# Power_managment.net
KiCad netlist of a schematic drawn in Altium Designer
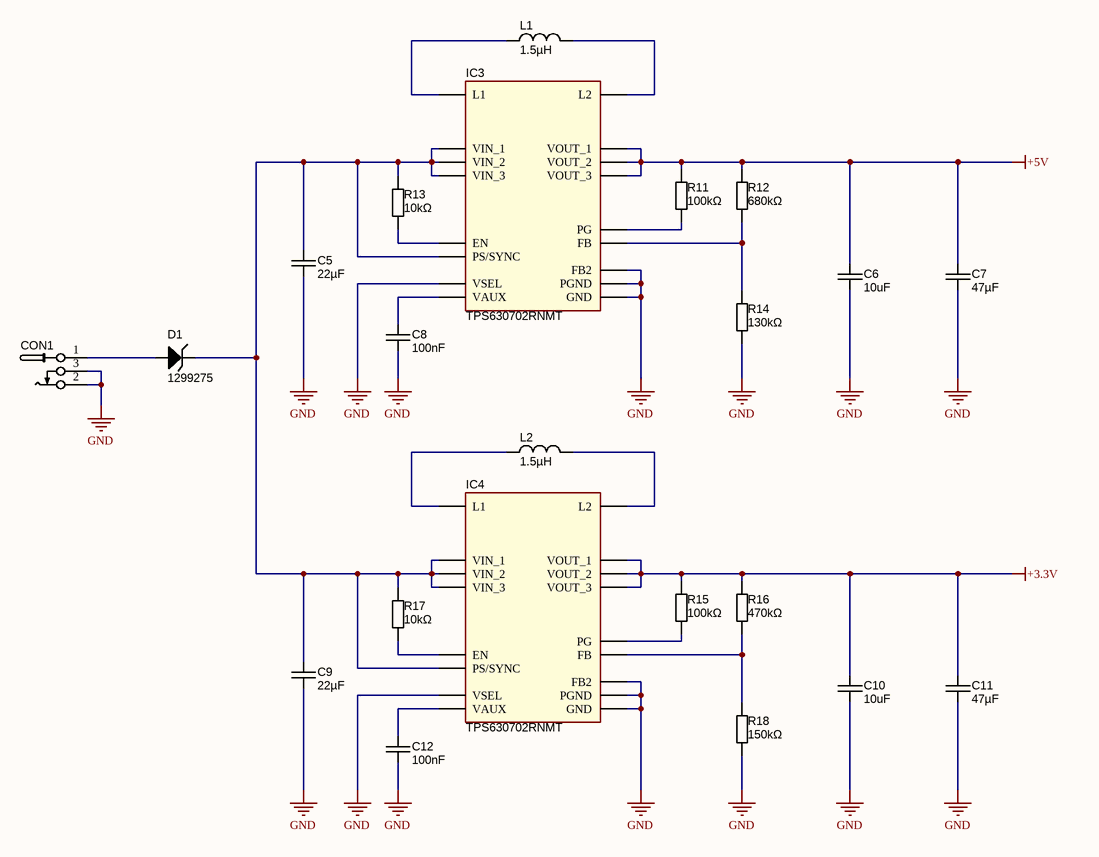
[diagram p0: Power managment.SchDoc]

(export (version "E")
  (design (tool "Eeschema 10.0.6"))
  (components
    (comp (ref "C5")
      (value "22µF")
      (footprint "CAPC3216N")
      (description "Capacitor SMD Cer 10uF 10% 16V X7R 1206")
      (fields (field (name "TOLERANCE") "±10%") (field (name "Comment") "approved sub OK"))
      (libsource (lib "Nejc Klanjšček") (part "CAPC_10u_1206_16V"))
    )
    (comp (ref "C6")
      (value "10uF")
      (footprint "CAPC1608N")
      (description "Capacitor SMD Cer 1uF 10% 16V X7R 0603")
      (fields (field (name "TOLERANCE") "±10%") (field (name "Comment") "approved sub OK"))
      (libsource (lib "Nejc Klanjšček") (part "CAPC_1u_0603"))
    )
    (comp (ref "C7")
      (value "47µF")
      (footprint "CAPC3216N")
      (description "Capacitor SMD Cer 10uF 10% 16V X7R 1206")
      (fields (field (name "TOLERANCE") "±10%") (field (name "Comment") "approved sub OK"))
      (libsource (lib "Nejc Klanjšček") (part "CAPC_10u_1206_16V"))
    )
    (comp (ref "C8")
      (value "100nF")
      (footprint "CAPC1608N")
      (description "Capacitor SMD Cer 1uF 10% 16V X7R 0603")
      (fields (field (name "TOLERANCE") "±10%") (field (name "Comment") "approved sub OK"))
      (libsource (lib "Nejc Klanjšček") (part "CAPC_1u_0603"))
    )
    (comp (ref "C9")
      (value "22µF")
      (footprint "CAPC3216N")
      (description "Capacitor SMD Cer 10uF 10% 16V X7R 1206")
      (fields (field (name "TOLERANCE") "±10%") (field (name "Comment") "approved sub OK"))
      (libsource (lib "Nejc Klanjšček") (part "CAPC_10u_1206_16V"))
    )
    (comp (ref "C10")
      (value "10uF")
      (footprint "CAPC1608N")
      (description "Capacitor SMD Cer 1uF 10% 16V X7R 0603")
      (fields (field (name "TOLERANCE") "±10%") (field (name "Comment") "approved sub OK"))
      (libsource (lib "Nejc Klanjšček") (part "CAPC_1u_0603"))
    )
    (comp (ref "C11")
      (value "47µF")
      (footprint "CAPC3216N")
      (description "Capacitor SMD Cer 10uF 10% 16V X7R 1206")
      (fields (field (name "TOLERANCE") "±10%") (field (name "Comment") "approved sub OK"))
      (libsource (lib "Nejc Klanjšček") (part "CAPC_10u_1206_16V"))
    )
    (comp (ref "C12")
      (value "100nF")
      (footprint "CAPC1608N")
      (description "Capacitor SMD Cer 1uF 10% 16V X7R 0603")
      (fields (field (name "TOLERANCE") "±10%") (field (name "Comment") "approved sub OK"))
      (libsource (lib "Nejc Klanjšček") (part "CAPC_1u_0603"))
    )
    (comp (ref "CON1")
      (value "12V")
      (footprint "FC68148S_2")
      (description "Power Connector, THT, 2.1mm ID, 5.5mm OD")
      (libsource (lib "Nejc Klanjšček") (part "CONN_PWR_JACK_2.1x5.5mm"))
    )
    (comp (ref "D1")
      (value "Unidirectional, 400 W, 100 VDC")
      (footprint "DO-214AC_Unidirectional")
      (description "WE-TVSP Power TVS Diode, Unidirectional, 400 W, 100 VDC")
      (fields
        (field (name "PARTNO") "824500102")
        (field (name "MANUFACTURER") "Wurth Elektronik")
        (field (name "SUPPLIER PART NUMBER 1") "1299275")
        (field (name "CREATED BY") "Baojun Chen")
      )
      (libsource (lib "Nejc Klanjšček") (part "WE-TVSP DO-214AC, 824500102"))
    )
    (comp (ref "IC3")
      (value "TPS630702RNMT")
      (footprint "TPS630702RNMT")
      (description "Integrated Circuit")
      (fields (field (name "MOUSER PART NUMBER") "595-TPS630702RNMT"))
      (libsource (lib "Nejc Klanjšček") (part "TPS630702RNMT"))
    )
    (comp (ref "IC4")
      (value "TPS630702RNMT")
      (footprint "TPS630702RNMT")
      (description "Integrated Circuit")
      (fields (field (name "MOUSER PART NUMBER") "595-TPS630702RNMT"))
      (libsource (lib "Nejc Klanjšček") (part "TPS630702RNMT"))
    )
    (comp (ref "L1")
      (value "1.5µH")
      (footprint "INDPM6965X300N")
      (description "Inductor SMD Low DCR 10 µH 900mA 20% 1210")
      (fields (field (name "TOLERANCE") "±20%"))
      (libsource (lib "Nejc Klanjšček") (part "INDC_1.5u"))
    )
    (comp (ref "L2")
      (value "1.5µH")
      (footprint "INDPM6965X300N")
      (description "Inductor SMD Low DCR 10 µH 900mA 20% 1210")
      (fields (field (name "TOLERANCE") "±20%"))
      (libsource (lib "Nejc Klanjšček") (part "INDC_1.5u"))
    )
    (comp (ref "R11")
      (value "100kΩ")
      (footprint "RESC1608N")
      (description "Resistor SMD chip 1.5k Ohm 0.1W 5% 0603")
      (fields (field (name "TOLERANCE") "±5%") (field (name "Comment") "Thick Film"))
      (libsource (lib "Nejc Klanjšček") (part "RES_1K5_0603_5%"))
    )
    (comp (ref "R12")
      (value "680kΩ")
      (footprint "RESC1608N")
      (description "Resistor SMD chip 1.5k Ohm 0.1W 5% 0603")
      (fields (field (name "TOLERANCE") "±5%") (field (name "Comment") "Thick Film"))
      (libsource (lib "Nejc Klanjšček") (part "RES_1K5_0603_5%"))
    )
    (comp (ref "R13")
      (value "10kΩ")
      (footprint "RESC1608N")
      (description "Resistor SMD chip 1.5k Ohm 0.1W 5% 0603")
      (fields (field (name "TOLERANCE") "±5%") (field (name "Comment") "Thick Film"))
      (libsource (lib "Nejc Klanjšček") (part "RES_1K5_0603_5%"))
    )
    (comp (ref "R14")
      (value "130kΩ")
      (footprint "RESC1608N")
      (description "Resistor SMD chip 1.5k Ohm 0.1W 5% 0603")
      (fields (field (name "TOLERANCE") "±5%") (field (name "Comment") "Thick Film"))
      (libsource (lib "Nejc Klanjšček") (part "RES_1K5_0603_5%"))
    )
    (comp (ref "R15")
      (value "100kΩ")
      (footprint "RESC1608N")
      (description "Resistor SMD chip 1.5k Ohm 0.1W 5% 0603")
      (fields (field (name "TOLERANCE") "±5%") (field (name "Comment") "Thick Film"))
      (libsource (lib "Nejc Klanjšček") (part "RES_1K5_0603_5%"))
    )
    (comp (ref "R16")
      (value "470kΩ")
      (footprint "RESC1608N")
      (description "Resistor SMD chip 1.5k Ohm 0.1W 5% 0603")
      (fields (field (name "TOLERANCE") "±5%") (field (name "Comment") "Thick Film"))
      (libsource (lib "Nejc Klanjšček") (part "RES_1K5_0603_5%"))
    )
    (comp (ref "R17")
      (value "10kΩ")
      (footprint "RESC1608N")
      (description "Resistor SMD chip 1.5k Ohm 0.1W 5% 0603")
      (fields (field (name "TOLERANCE") "±5%") (field (name "Comment") "Thick Film"))
      (libsource (lib "Nejc Klanjšček") (part "RES_1K5_0603_5%"))
    )
    (comp (ref "R18")
      (value "150kΩ")
      (footprint "RESC1608N")
      (description "Resistor SMD chip 1.5k Ohm 0.1W 5% 0603")
      (fields (field (name "TOLERANCE") "±5%") (field (name "Comment") "Thick Film"))
      (libsource (lib "Nejc Klanjšček") (part "RES_1K5_0603_5%"))
    )
  )
  (nets
    (net (code "1") (name "+3.3V") (class "Default")
      (node (ref "C10") (pin "2") (pintype "passive"))
      (node (ref "C11") (pin "1") (pintype "passive"))
      (node (ref "IC4") (pin "7") (pinfunction "VOUT_1_7") (pintype "passive"))
      (node (ref "IC4") (pin "8") (pinfunction "VOUT_2_8") (pintype "passive"))
      (node (ref "IC4") (pin "A7") (pinfunction "VOUT_3_A7") (pintype "passive"))
      (node (ref "R15") (pin "2") (pinfunction "2_2") (pintype "passive"))
      (node (ref "R16") (pin "2") (pinfunction "2_2") (pintype "passive"))
    )
    (net (code "2") (name "+5V") (class "Default")
      (node (ref "C6") (pin "2") (pintype "passive"))
      (node (ref "C7") (pin "1") (pintype "passive"))
      (node (ref "IC3") (pin "7") (pinfunction "VOUT_1_7") (pintype "passive"))
      (node (ref "IC3") (pin "8") (pinfunction "VOUT_2_8") (pintype "passive"))
      (node (ref "IC3") (pin "A7") (pinfunction "VOUT_3_A7") (pintype "passive"))
      (node (ref "R11") (pin "2") (pinfunction "2_2") (pintype "passive"))
      (node (ref "R12") (pin "2") (pinfunction "2_2") (pintype "passive"))
    )
    (net (code "3") (name "GND") (class "Default")
      (node (ref "C10") (pin "1") (pintype "passive"))
      (node (ref "C11") (pin "2") (pintype "passive"))
      (node (ref "C12") (pin "1") (pintype "passive"))
      (node (ref "C5") (pin "2") (pintype "passive"))
      (node (ref "C6") (pin "1") (pintype "passive"))
      (node (ref "C7") (pin "2") (pintype "passive"))
      (node (ref "C8") (pin "1") (pintype "passive"))
      (node (ref "C9") (pin "2") (pintype "passive"))
      (node (ref "CON1") (pin "2") (pinfunction "2_2") (pintype "passive"))
      (node (ref "CON1") (pin "3") (pinfunction "3_3") (pintype "passive"))
      (node (ref "IC3") (pin "10") (pinfunction "PGND_10") (pintype "passive"))
      (node (ref "IC3") (pin "15") (pinfunction "VSEL_15") (pintype "passive"))
      (node (ref "IC3") (pin "4") (pinfunction "GND_4") (pintype "passive"))
      (node (ref "IC3") (pin "6") (pinfunction "FB2_6") (pintype "passive"))
      (node (ref "IC4") (pin "10") (pinfunction "PGND_10") (pintype "passive"))
      (node (ref "IC4") (pin "15") (pinfunction "VSEL_15") (pintype "passive"))
      (node (ref "IC4") (pin "4") (pinfunction "GND_4") (pintype "passive"))
      (node (ref "IC4") (pin "6") (pinfunction "FB2_6") (pintype "passive"))
      (node (ref "R14") (pin "1") (pinfunction "1_1") (pintype "passive"))
      (node (ref "R18") (pin "1") (pinfunction "1_1") (pintype "passive"))
    )
    (net (code "4") (name "Net-(CON1-Pad1)") (class "Default")
      (node (ref "CON1") (pin "1") (pinfunction "1_1") (pintype "passive"))
      (node (ref "D1") (pin "2") (pinfunction "2_2") (pintype "passive"))
    )
    (net (code "5") (name "Net-(IC3-EN)") (class "Default")
      (node (ref "IC3") (pin "14") (pinfunction "EN_14") (pintype "passive"))
      (node (ref "R13") (pin "1") (pinfunction "1_1") (pintype "passive"))
    )
    (net (code "6") (name "Net-(IC3-FB)") (class "Default")
      (node (ref "IC3") (pin "5") (pinfunction "FB_5") (pintype "passive"))
      (node (ref "R12") (pin "1") (pinfunction "1_1") (pintype "passive"))
      (node (ref "R14") (pin "2") (pinfunction "2_2") (pintype "passive"))
    )
    (net (code "7") (name "Net-(IC3-L1)") (class "Default")
      (node (ref "IC3") (pin "11") (pinfunction "L1_11") (pintype "passive"))
      (node (ref "L1") (pin "1") (pinfunction "1_1") (pintype "passive"))
    )
    (net (code "8") (name "Net-(IC3-L2)") (class "Default")
      (node (ref "IC3") (pin "9") (pinfunction "L2_9") (pintype "passive"))
      (node (ref "L1") (pin "2") (pinfunction "2_2") (pintype "passive"))
    )
    (net (code "9") (name "Net-(IC3-PG)") (class "Default")
      (node (ref "IC3") (pin "2") (pinfunction "PG_2") (pintype "passive"))
      (node (ref "R11") (pin "1") (pinfunction "1_1") (pintype "passive"))
    )
    (net (code "10") (name "Net-(IC3-PS{slash}SYNC)") (class "Default")
      (node (ref "C5") (pin "1") (pintype "passive"))
      (node (ref "C9") (pin "1") (pintype "passive"))
      (node (ref "D1") (pin "1") (pinfunction "1_1") (pintype "passive"))
      (node (ref "IC3") (pin "1") (pinfunction "PS/SYNC_1") (pintype "passive"))
      (node (ref "IC3") (pin "12") (pinfunction "VIN_1_12") (pintype "passive"))
      (node (ref "IC3") (pin "13") (pinfunction "VIN_2_13") (pintype "passive"))
      (node (ref "IC3") (pin "A12") (pinfunction "VIN_3_A12") (pintype "passive"))
      (node (ref "IC4") (pin "1") (pinfunction "PS/SYNC_1") (pintype "passive"))
      (node (ref "IC4") (pin "12") (pinfunction "VIN_1_12") (pintype "passive"))
      (node (ref "IC4") (pin "13") (pinfunction "VIN_2_13") (pintype "passive"))
      (node (ref "IC4") (pin "A12") (pinfunction "VIN_3_A12") (pintype "passive"))
      (node (ref "R13") (pin "2") (pinfunction "2_2") (pintype "passive"))
      (node (ref "R17") (pin "2") (pinfunction "2_2") (pintype "passive"))
    )
    (net (code "11") (name "Net-(IC3-VAUX)") (class "Default")
      (node (ref "C8") (pin "2") (pintype "passive"))
      (node (ref "IC3") (pin "3") (pinfunction "VAUX_3") (pintype "passive"))
    )
    (net (code "12") (name "Net-(IC4-EN)") (class "Default")
      (node (ref "IC4") (pin "14") (pinfunction "EN_14") (pintype "passive"))
      (node (ref "R17") (pin "1") (pinfunction "1_1") (pintype "passive"))
    )
    (net (code "13") (name "Net-(IC4-FB)") (class "Default")
      (node (ref "IC4") (pin "5") (pinfunction "FB_5") (pintype "passive"))
      (node (ref "R16") (pin "1") (pinfunction "1_1") (pintype "passive"))
      (node (ref "R18") (pin "2") (pinfunction "2_2") (pintype "passive"))
    )
    (net (code "14") (name "Net-(IC4-L1)") (class "Default")
      (node (ref "IC4") (pin "11") (pinfunction "L1_11") (pintype "passive"))
      (node (ref "L2") (pin "1") (pinfunction "1_1") (pintype "passive"))
    )
    (net (code "15") (name "Net-(IC4-L2)") (class "Default")
      (node (ref "IC4") (pin "9") (pinfunction "L2_9") (pintype "passive"))
      (node (ref "L2") (pin "2") (pinfunction "2_2") (pintype "passive"))
    )
    (net (code "16") (name "Net-(IC4-PG)") (class "Default")
      (node (ref "IC4") (pin "2") (pinfunction "PG_2") (pintype "passive"))
      (node (ref "R15") (pin "1") (pinfunction "1_1") (pintype "passive"))
    )
    (net (code "17") (name "Net-(IC4-VAUX)") (class "Default")
      (node (ref "C12") (pin "2") (pintype "passive"))
      (node (ref "IC4") (pin "3") (pinfunction "VAUX_3") (pintype "passive"))
    )
  )
)
